# 16_FLAGS_Z_S.net
KiCad netlist of a schematic drawn in EAGLE
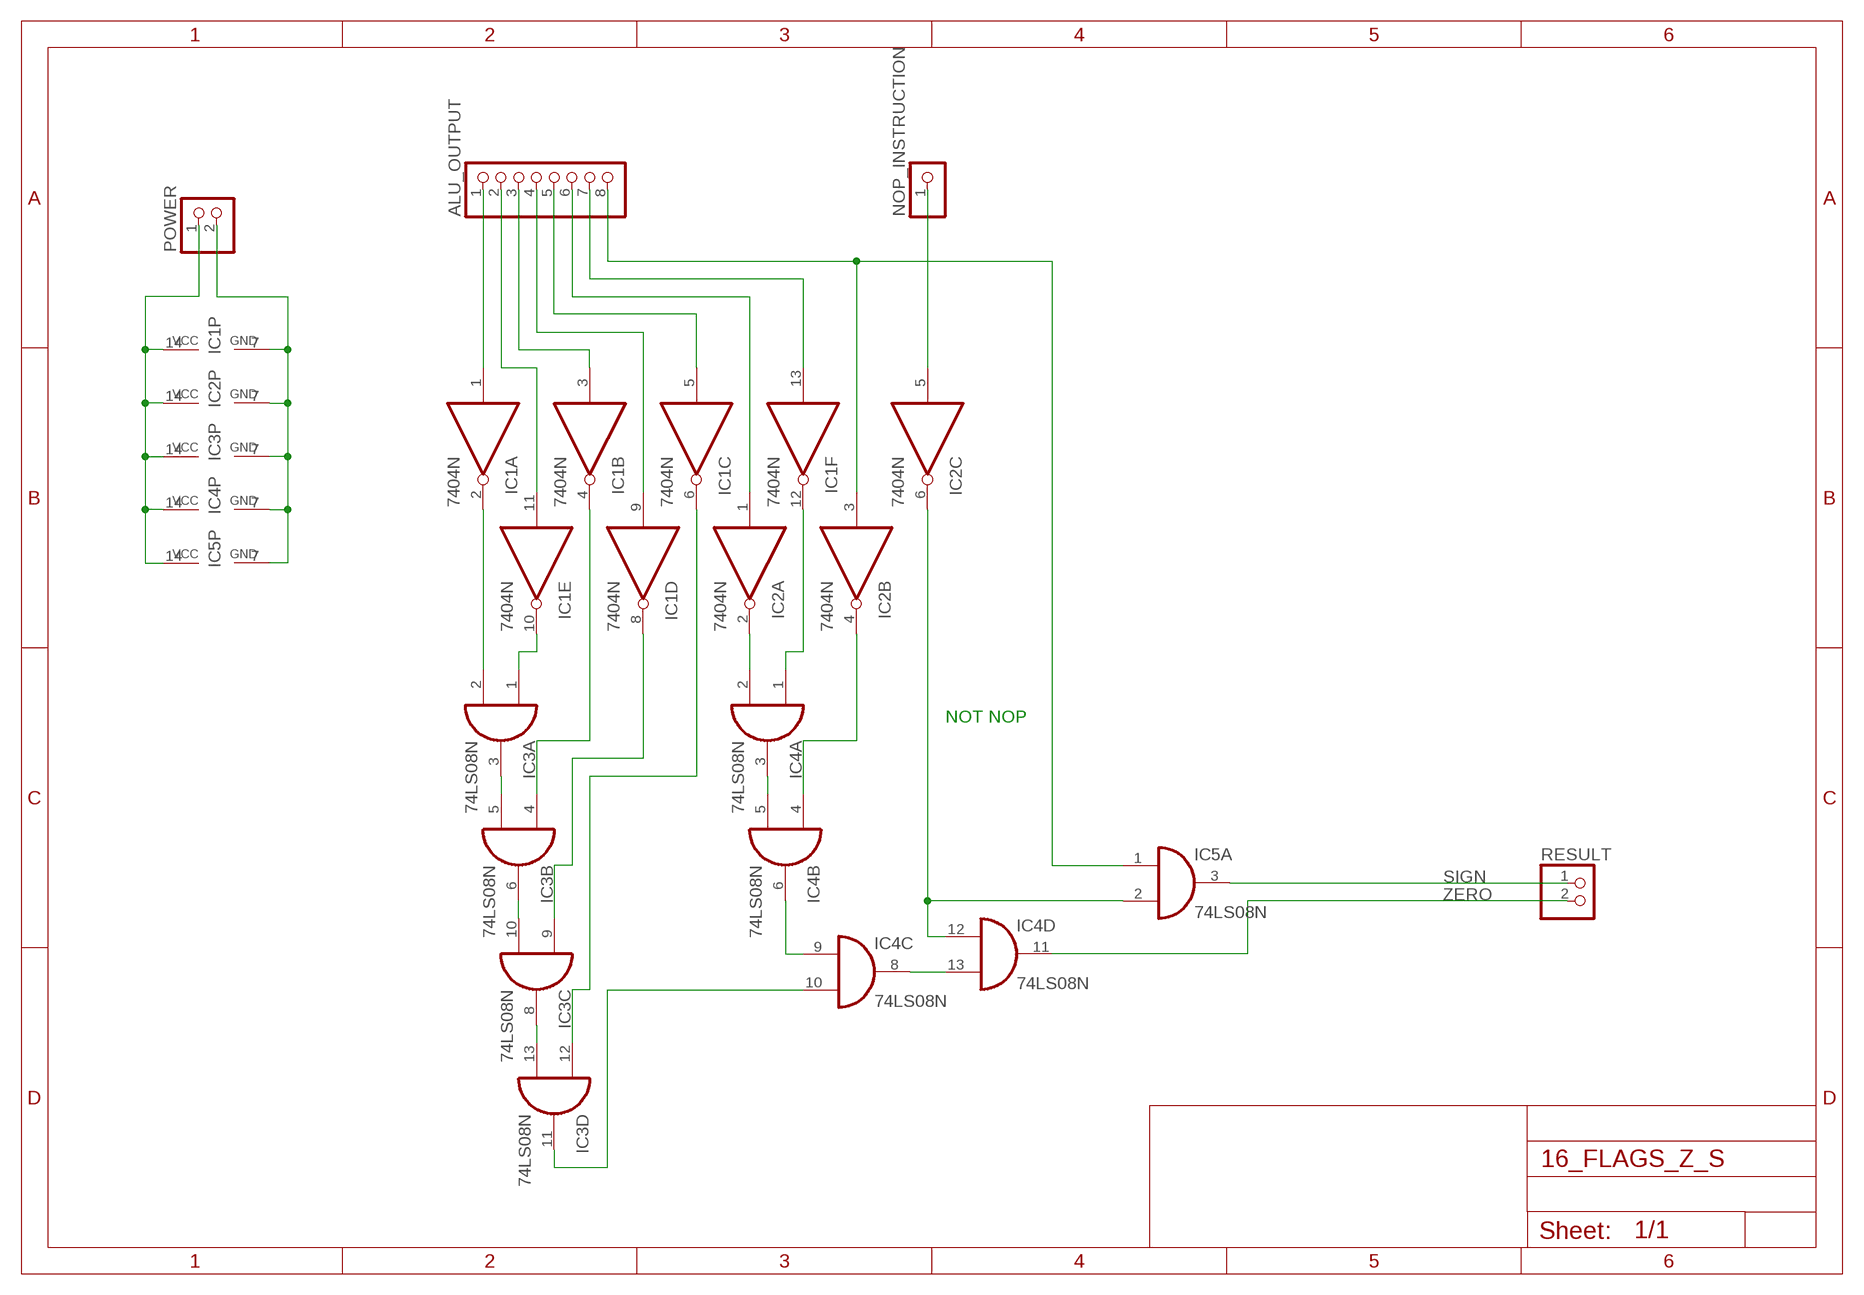
[diagram p0: schematic, sheet 1]

(export (version "E")
  (design (tool "Eeschema 10.0.6"))
  (components
    (comp (ref "ALU_OUTPUT")
      (value "PINHD-1X8")
      (footprint "eagle-import:1X08")
      (libsource (lib "eagle-import") (part "PINHD-1X8"))
    )
    (comp (ref "IC1")
      (value "7404N")
      (footprint "eagle-import:DIL14")
      (libsource (lib "eagle-import") (part "7404N"))
    )
    (comp (ref "IC2")
      (value "7404N")
      (footprint "eagle-import:DIL14")
      (libsource (lib "eagle-import") (part "7404N"))
    )
    (comp (ref "IC3")
      (value "74LS08N")
      (footprint "eagle-import:DIL14")
      (libsource (lib "eagle-import") (part "7408NLS"))
    )
    (comp (ref "IC4")
      (value "74LS08N")
      (footprint "eagle-import:DIL14")
      (libsource (lib "eagle-import") (part "7408NLS"))
    )
    (comp (ref "IC5")
      (value "74LS08N")
      (footprint "eagle-import:DIL14")
      (libsource (lib "eagle-import") (part "7408NLS"))
    )
    (comp (ref "NOP_INSTRUCTION")
      (value "PINHD-1X1")
      (footprint "eagle-import:1X01")
      (libsource (lib "eagle-import") (part "PINHD-1X1"))
    )
    (comp (ref "POWER")
      (value "PINHD-1X2")
      (footprint "eagle-import:1X02")
      (libsource (lib "eagle-import") (part "PINHD-1X2"))
    )
    (comp (ref "RESULT")
      (value "PINHD-1X2")
      (footprint "eagle-import:1X02")
      (libsource (lib "eagle-import") (part "PINHD-1X2"))
    )
  )
  (nets
    (net (code "1") (name "/SIGN") (class "Default")
      (node (ref "IC5") (pin "3") (pinfunction "O_3") (pintype "output"))
      (node (ref "RESULT") (pin "1") (pinfunction "1_1") (pintype "passive"))
    )
    (net (code "2") (name "/ZERO") (class "Default")
      (node (ref "IC4") (pin "11") (pinfunction "O_11") (pintype "output"))
      (node (ref "RESULT") (pin "2") (pinfunction "2_2") (pintype "passive"))
    )
    (net (code "3") (name "Net-(IC1A-I)") (class "Default")
      (node (ref "ALU_OUTPUT") (pin "1") (pinfunction "1_1") (pintype "passive"))
      (node (ref "IC1") (pin "1") (pinfunction "I_1") (pintype "input"))
    )
    (net (code "4") (name "Net-(IC1A-O)") (class "Default")
      (node (ref "IC1") (pin "2") (pinfunction "O_2") (pintype "output"))
      (node (ref "IC3") (pin "2") (pinfunction "I1_2") (pintype "input"))
    )
    (net (code "5") (name "Net-(IC1B-I)") (class "Default")
      (node (ref "ALU_OUTPUT") (pin "3") (pinfunction "3_3") (pintype "passive"))
      (node (ref "IC1") (pin "3") (pinfunction "I_3") (pintype "input"))
    )
    (net (code "6") (name "Net-(IC1B-O)") (class "Default")
      (node (ref "IC1") (pin "4") (pinfunction "O_4") (pintype "output"))
      (node (ref "IC3") (pin "4") (pinfunction "I0_4") (pintype "input"))
    )
    (net (code "7") (name "Net-(IC1C-I)") (class "Default")
      (node (ref "ALU_OUTPUT") (pin "5") (pinfunction "5_5") (pintype "passive"))
      (node (ref "IC1") (pin "5") (pinfunction "I_5") (pintype "input"))
    )
    (net (code "8") (name "Net-(IC1C-O)") (class "Default")
      (node (ref "IC1") (pin "6") (pinfunction "O_6") (pintype "output"))
      (node (ref "IC3") (pin "12") (pinfunction "I0_12") (pintype "input"))
    )
    (net (code "9") (name "Net-(IC1D-I)") (class "Default")
      (node (ref "ALU_OUTPUT") (pin "4") (pinfunction "4_4") (pintype "passive"))
      (node (ref "IC1") (pin "9") (pinfunction "I_9") (pintype "input"))
    )
    (net (code "10") (name "Net-(IC1D-O)") (class "Default")
      (node (ref "IC1") (pin "8") (pinfunction "O_8") (pintype "output"))
      (node (ref "IC3") (pin "9") (pinfunction "I0_9") (pintype "input"))
    )
    (net (code "11") (name "Net-(IC1E-I)") (class "Default")
      (node (ref "ALU_OUTPUT") (pin "2") (pinfunction "2_2") (pintype "passive"))
      (node (ref "IC1") (pin "11") (pinfunction "I_11") (pintype "input"))
    )
    (net (code "12") (name "Net-(IC1E-O)") (class "Default")
      (node (ref "IC1") (pin "10") (pinfunction "O_10") (pintype "output"))
      (node (ref "IC3") (pin "1") (pinfunction "I0_1") (pintype "input"))
    )
    (net (code "13") (name "Net-(IC1F-I)") (class "Default")
      (node (ref "ALU_OUTPUT") (pin "7") (pinfunction "7_7") (pintype "passive"))
      (node (ref "IC1") (pin "13") (pinfunction "I_13") (pintype "input"))
    )
    (net (code "14") (name "Net-(IC1F-O)") (class "Default")
      (node (ref "IC1") (pin "12") (pinfunction "O_12") (pintype "output"))
      (node (ref "IC4") (pin "1") (pinfunction "I0_1") (pintype "input"))
    )
    (net (code "15") (name "Net-(IC1G-GND)") (class "Default")
      (node (ref "IC1") (pin "7") (pinfunction "GND_7") (pintype "power_in"))
      (node (ref "IC2") (pin "7") (pinfunction "GND_7") (pintype "power_in"))
      (node (ref "IC3") (pin "7") (pinfunction "GND_7") (pintype "power_in"))
      (node (ref "IC4") (pin "7") (pinfunction "GND_7") (pintype "power_in"))
      (node (ref "IC5") (pin "7") (pinfunction "GND_7") (pintype "power_in"))
      (node (ref "POWER") (pin "2") (pinfunction "2_2") (pintype "passive"))
    )
    (net (code "16") (name "Net-(IC1G-VCC)") (class "Default")
      (node (ref "IC1") (pin "14") (pinfunction "VCC_14") (pintype "power_in"))
      (node (ref "IC2") (pin "14") (pinfunction "VCC_14") (pintype "power_in"))
      (node (ref "IC3") (pin "14") (pinfunction "VCC_14") (pintype "power_in"))
      (node (ref "IC4") (pin "14") (pinfunction "VCC_14") (pintype "power_in"))
      (node (ref "IC5") (pin "14") (pinfunction "VCC_14") (pintype "power_in"))
      (node (ref "POWER") (pin "1") (pinfunction "1_1") (pintype "passive"))
    )
    (net (code "17") (name "Net-(IC2A-I)") (class "Default")
      (node (ref "ALU_OUTPUT") (pin "6") (pinfunction "6_6") (pintype "passive"))
      (node (ref "IC2") (pin "1") (pinfunction "I_1") (pintype "input"))
    )
    (net (code "18") (name "Net-(IC2A-O)") (class "Default")
      (node (ref "IC2") (pin "2") (pinfunction "O_2") (pintype "output"))
      (node (ref "IC4") (pin "2") (pinfunction "I1_2") (pintype "input"))
    )
    (net (code "19") (name "Net-(IC2B-I)") (class "Default")
      (node (ref "ALU_OUTPUT") (pin "8") (pinfunction "8_8") (pintype "passive"))
      (node (ref "IC2") (pin "3") (pinfunction "I_3") (pintype "input"))
      (node (ref "IC5") (pin "1") (pinfunction "I0_1") (pintype "input"))
    )
    (net (code "20") (name "Net-(IC2B-O)") (class "Default")
      (node (ref "IC2") (pin "4") (pinfunction "O_4") (pintype "output"))
      (node (ref "IC4") (pin "4") (pinfunction "I0_4") (pintype "input"))
    )
    (net (code "21") (name "Net-(IC2C-I)") (class "Default")
      (node (ref "IC2") (pin "5") (pinfunction "I_5") (pintype "input"))
      (node (ref "NOP_INSTRUCTION") (pin "1") (pinfunction "1_1") (pintype "passive"))
    )
    (net (code "22") (name "Net-(IC2C-O)") (class "Default")
      (node (ref "IC2") (pin "6") (pinfunction "O_6") (pintype "output"))
      (node (ref "IC4") (pin "12") (pinfunction "I0_12") (pintype "input"))
      (node (ref "IC5") (pin "2") (pinfunction "I1_2") (pintype "input"))
    )
    (net (code "23") (name "Net-(IC3A-O)") (class "Default")
      (node (ref "IC3") (pin "3") (pinfunction "O_3") (pintype "output"))
      (node (ref "IC3") (pin "5") (pinfunction "I1_5") (pintype "input"))
    )
    (net (code "24") (name "Net-(IC3B-O)") (class "Default")
      (node (ref "IC3") (pin "10") (pinfunction "I1_10") (pintype "input"))
      (node (ref "IC3") (pin "6") (pinfunction "O_6") (pintype "output"))
    )
    (net (code "25") (name "Net-(IC3C-O)") (class "Default")
      (node (ref "IC3") (pin "13") (pinfunction "I1_13") (pintype "input"))
      (node (ref "IC3") (pin "8") (pinfunction "O_8") (pintype "output"))
    )
    (net (code "26") (name "Net-(IC3D-O)") (class "Default")
      (node (ref "IC3") (pin "11") (pinfunction "O_11") (pintype "output"))
      (node (ref "IC4") (pin "10") (pinfunction "I1_10") (pintype "input"))
    )
    (net (code "27") (name "Net-(IC4A-O)") (class "Default")
      (node (ref "IC4") (pin "3") (pinfunction "O_3") (pintype "output"))
      (node (ref "IC4") (pin "5") (pinfunction "I1_5") (pintype "input"))
    )
    (net (code "28") (name "Net-(IC4B-O)") (class "Default")
      (node (ref "IC4") (pin "6") (pinfunction "O_6") (pintype "output"))
      (node (ref "IC4") (pin "9") (pinfunction "I0_9") (pintype "input"))
    )
    (net (code "29") (name "Net-(IC4C-O)") (class "Default")
      (node (ref "IC4") (pin "13") (pinfunction "I1_13") (pintype "input"))
      (node (ref "IC4") (pin "8") (pinfunction "O_8") (pintype "output"))
    )
  )
)
